# Pre-amp.net
KiCad netlist of a schematic drawn in Altium Designer
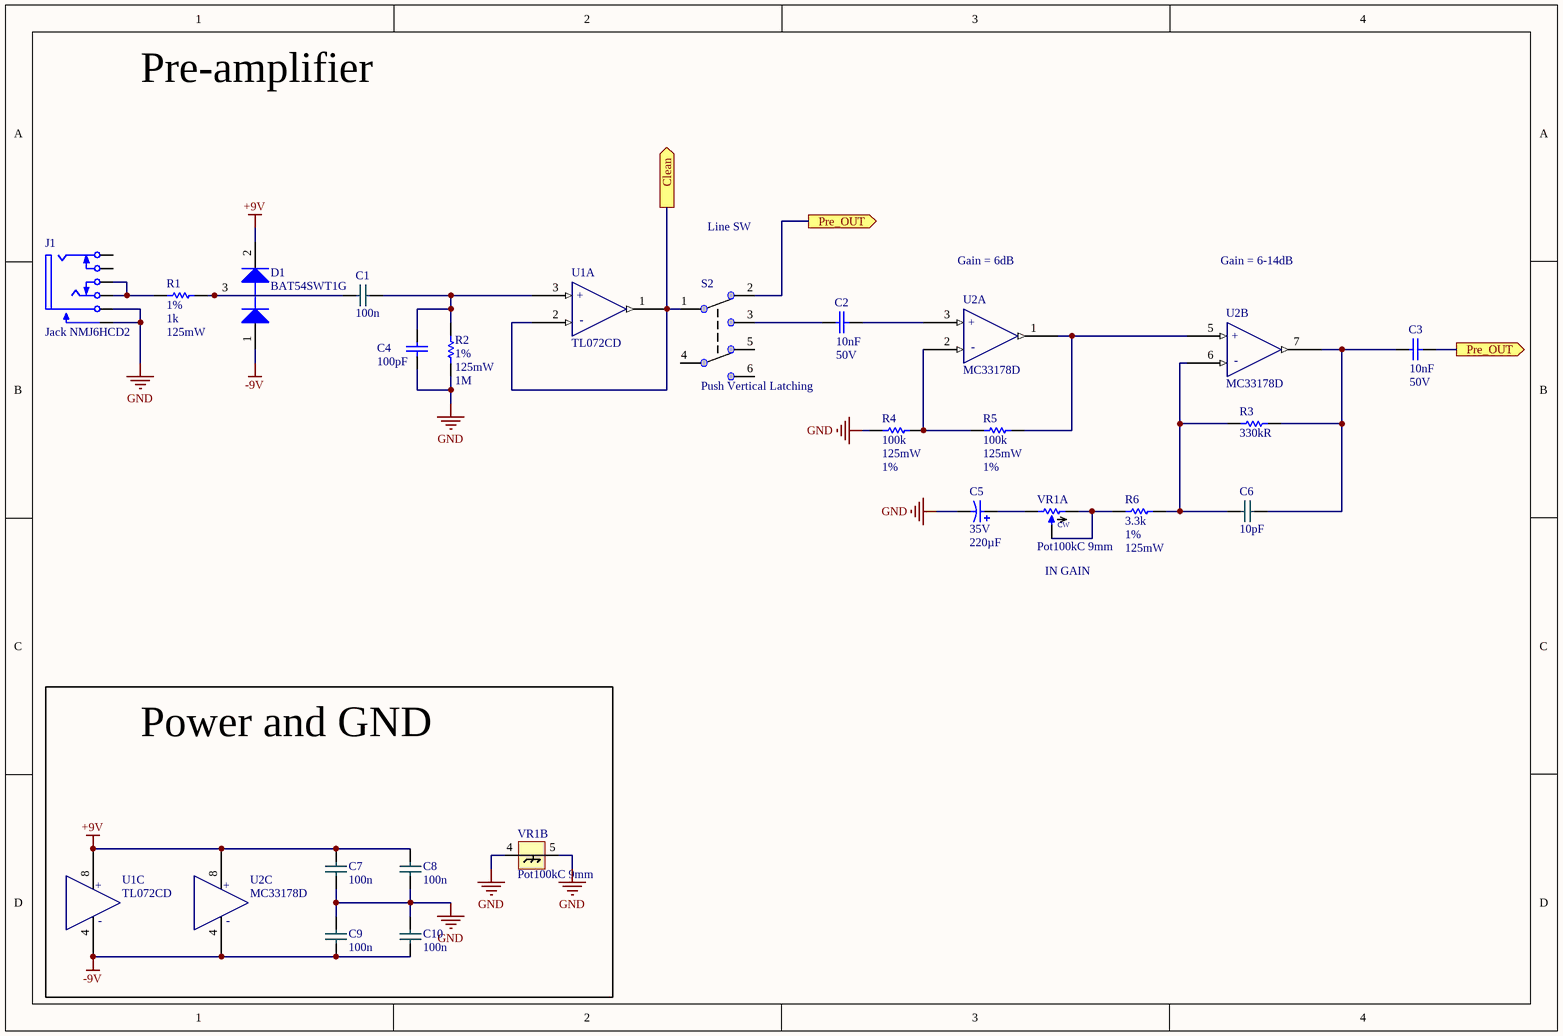
[diagram p0: Pre-amp.SchDoc]

(export (version "E")
  (design (tool "Eeschema 10.0.6"))
  (components
    (comp (ref "C1")
      (value "100n")
      (footprint "0805-CAP")
      (description "0.1uF 25volts C0G 5%")
      (fields
        (field (name "MOUSER PART") "81-GRM31C5C1E104JA01")
        (field (name "Comment") "Cap 0805 100nF 4")
        (field (name "PUBLISHER") "Altium Limited")
      )
      (libsource (lib "Darkglass Electronics") (part "Capacitor NP"))
    )
    (comp (ref "C2")
      (value "Cap 10nF 0805 C0G")
      (footprint "0805-CAP")
      (description "Cap 10nF 0805 C0G 50V +-5%")
      (fields (field (name "CAPACITANCE") "10nF") (field (name "RATED VOLTAGE") "50V"))
      (libsource (lib "Darkglass Electronics") (part "Capacitor Non-polarized"))
    )
    (comp (ref "C3")
      (value "Cap 10nF 0805 C0G")
      (footprint "0805-CAP")
      (description "Cap 10nF 0805 C0G 50V +-5%")
      (fields (field (name "CAPACITANCE") "10nF") (field (name "RATED VOLTAGE") "50V"))
      (libsource (lib "Darkglass Electronics") (part "Capacitor Non-polarized"))
    )
    (comp (ref "C4")
      (value "Cap 100pF 0603 C0G")
      (footprint "0603-CAP")
      (description "Cap 100pF 0603 C0G 50V +-5%")
      (fields (field (name "CAPACITANCE") "100pF"))
      (libsource (lib "Darkglass Electronics") (part "Capacitor Non-polarized"))
    )
    (comp (ref "C5")
      (value "Cap pol 220µF 35V")
      (footprint "E-CAP, SMT, diameter 10mm, height 10.2mm")
      (description "Cap Aluminum 220uF 35V ±20% (10x10.2mm) SMD 2000h 85°C")
      (fields (field (name "RATED VOLTAGE") "35V") (field (name "CAPACITANCE") "220µF"))
      (libsource (lib "Darkglass Electronics") (part "Capacitor Polarized"))
    )
    (comp (ref "C6")
      (value "cap 0805 10pF")
      (footprint "0805-CAP")
      (fields (field (name "CAPACITANCE") "10pF"))
      (libsource (lib "Darkglass Electronics") (part "Capacitor NP"))
    )
    (comp (ref "C7")
      (value "100n")
      (footprint "0805-CAP")
      (description "0.1uF 25volts C0G 5%")
      (fields
        (field (name "MOUSER PART") "81-GRM31C5C1E104JA01")
        (field (name "Comment") "Cap 0805 100nF 4")
        (field (name "PUBLISHER") "Altium Limited")
      )
      (libsource (lib "Darkglass Electronics") (part "Capacitor NP"))
    )
    (comp (ref "C8")
      (value "100n")
      (footprint "0805-CAP")
      (description "0.1uF 25volts C0G 5%")
      (fields
        (field (name "MOUSER PART") "81-GRM31C5C1E104JA01")
        (field (name "Comment") "Cap 0805 100nF 4")
        (field (name "PUBLISHER") "Altium Limited")
      )
      (libsource (lib "Darkglass Electronics") (part "Capacitor NP"))
    )
    (comp (ref "C9")
      (value "100n")
      (footprint "0805-CAP")
      (description "0.1uF 25volts C0G 5%")
      (fields
        (field (name "MOUSER PART") "81-GRM31C5C1E104JA01")
        (field (name "Comment") "Cap 0805 100nF 4")
        (field (name "PUBLISHER") "Altium Limited")
      )
      (libsource (lib "Darkglass Electronics") (part "Capacitor NP"))
    )
    (comp (ref "C10")
      (value "100n")
      (footprint "0805-CAP")
      (description "0.1uF 25volts C0G 5%")
      (fields
        (field (name "MOUSER PART") "81-GRM31C5C1E104JA01")
        (field (name "Comment") "Cap 0805 100nF 4")
        (field (name "PUBLISHER") "Altium Limited")
      )
      (libsource (lib "Darkglass Electronics") (part "Capacitor NP"))
    )
    (comp (ref "D1")
      (value "BAT54SWT1G")
      (footprint "ONSC-SOT-323-3-419-04_V")
      (description "Rectifier Diode, Schottky, 2 Element, 0.2A, 30V V(RRM), Silicon")
      (libsource (lib "Darkglass Electronics") (part "ONSC-D-A1K2C3-3"))
    )
    (comp (ref "J1")
      (value "Jack NMJ6HCD2")
      (footprint "Neutrik Jack metal nut")
      (description "Jack 1/4 stereo switched - PCBH - chrome nut")
      (fields (field (name "MANUFACTURER") "Neutrik") (field (name "DARKGLASS PART") "D00-0011"))
      (libsource (lib "Darkglass Electronics") (part "Symbol"))
    )
    (comp (ref "R1")
      (value "Res 1k 1% 0805")
      (footprint "0805-RES")
      (description "Resistor 1k +-1% 0805 Thin film 0.125W +-50ppm/°C")
      (fields
        (field (name "TOLERANCE (+-)") "1%")
        (field (name "RESISTANCE") "1k")
        (field (name "POWER") "125mW")
      )
      (libsource (lib "Darkglass Electronics") (part "Resistor"))
    )
    (comp (ref "R2")
      (value "Res 1M 1% 0805")
      (footprint "0805-RES")
      (description "Resistor 1M +-1% 0805 Thin film 0.125W +-50ppm/°C")
      (fields
        (field (name "TOLERANCE (+-)") "1%")
        (field (name "POWER") "125mW")
        (field (name "RESISTANCE") "1M")
      )
      (libsource (lib "Darkglass Electronics") (part "Resistor"))
    )
    (comp (ref "R3")
      (value "Res 0805 330k 1%")
      (footprint "0805-RES")
      (description "330kohm, 125mW, 1%, thin film")
      (fields
        (field (name "RESISTANCE") "330kR")
        (field (name "TOLERANCE") "1%")
        (field (name "PUBLISHER") "Altium Limited")
      )
      (libsource (lib "Darkglass Electronics") (part "RES"))
    )
    (comp (ref "R4")
      (value "Res 100k 1% 0805")
      (footprint "0805-RES")
      (description "Resistor 100k +-1% 0805 Thin film 0.125W +-50ppm/°C")
      (fields
        (field (name "RESISTANCE") "100k")
        (field (name "POWER") "125mW")
        (field (name "TOLERANCE (+-)") "1%")
      )
      (libsource (lib "Darkglass Electronics") (part "Resistor"))
    )
    (comp (ref "R5")
      (value "Res 100k 1% 0805")
      (footprint "0805-RES")
      (description "Resistor 100k +-1% 0805 Thin film 0.125W +-50ppm/°C")
      (fields
        (field (name "RESISTANCE") "100k")
        (field (name "POWER") "125mW")
        (field (name "TOLERANCE (+-)") "1%")
      )
      (libsource (lib "Darkglass Electronics") (part "Resistor"))
    )
    (comp (ref "R6")
      (value "Res 3.3k 1% 0805")
      (footprint "0805-RES")
      (description "Resistor 3.3k +-1% 0805 Thin film 0.125W +-50ppm/°C")
      (fields
        (field (name "RESISTANCE") "3.3k")
        (field (name "TOLERANCE (+-)") "1%")
        (field (name "POWER") "125mW")
      )
      (libsource (lib "Darkglass Electronics") (part "Resistor"))
    )
    (comp (ref "S2")
      (value "Push Vertical Latching")
      (footprint "PUSH VERTICAL DPDT")
      (description "DPDT Pushbutton Latching")
      (fields
        (field (name "MANUFACTURER PART NUMBER") "TL2201EEXA")
        (field (name "DARKGLASS PART") "D00-0005")
      )
      (libsource (lib "Darkglass Electronics") (part "Push Vertical"))
    )
    (comp (ref "U1")
      (value "TL072CD")
      (footprint "SOIC8-127P600X175-8N")
      (description "Operational Amplifiers - Op Amps Dual Low Noise JFET SOIC8")
      (libsource (lib "Darkglass Electronics") (part "TL072CD"))
    )
    (comp (ref "U2")
      (value "MC33178D")
      (footprint "SOIC8-127P600X175-8N")
      (description "IC OPAMP GP 5MHZ 8SOIC")
      (fields (field (name "MANUFACTURER") "ON Semiconductor") (field (name "MOUSER PART") "863-MC33178DG"))
      (libsource (lib "") (part "Symbol_1"))
    )
    (comp (ref "VR1")
      (value "Pot100kC 9mm")
      (footprint "LJV 9mm pot")
      (description "LJV 9mm pot")
      (fields (field (name "DARKGLASS PART") "D00-0002"))
      (libsource (lib "") (part "Pot100kC 9mm_1"))
    )
  )
  (nets
    (net (code "1") (name "+9V") (class "Default")
      (node (ref "C7") (pin "2") (pinfunction "2_2") (pintype "passive"))
      (node (ref "C8") (pin "2") (pinfunction "2_2") (pintype "passive"))
      (node (ref "D1") (pin "2") (pinfunction "K_2") (pintype "passive"))
      (node (ref "U1") (pin "8") (pinfunction "V+_8") (pintype "power_in"))
      (node (ref "U2") (pin "8") (pinfunction "8_8") (pintype "power_in"))
    )
    (net (code "2") (name "-9V") (class "Default")
      (node (ref "C10") (pin "1") (pinfunction "1_1") (pintype "passive"))
      (node (ref "C9") (pin "1") (pinfunction "1_1") (pintype "passive"))
      (node (ref "D1") (pin "1") (pinfunction "A_1") (pintype "passive"))
      (node (ref "U1") (pin "4") (pinfunction "V-_4") (pintype "power_in"))
      (node (ref "U2") (pin "4") (pinfunction "4_4") (pintype "power_in"))
    )
    (net (code "3") (name "/Clean") (class "Default")
      (node (ref "S2") (pin "1") (pinfunction "1_1") (pintype "passive"))
      (node (ref "U1") (pin "1") (pinfunction "OUT_1") (pintype "output"))
      (node (ref "U1") (pin "2") (pinfunction "IN-_2") (pintype "input"))
    )
    (net (code "4") (name "/Pre_OUT") (class "Default")
      (node (ref "C3") (pin "2") (pinfunction "2_2") (pintype "passive"))
      (node (ref "S2") (pin "2") (pinfunction "2_2") (pintype "passive"))
    )
    (net (code "5") (name "GND") (class "Default")
      (node (ref "C10") (pin "2") (pinfunction "2_2") (pintype "passive"))
      (node (ref "C4") (pin "2") (pinfunction "2_2") (pintype "passive"))
      (node (ref "C5") (pin "2") (pinfunction "2_2") (pintype "passive"))
      (node (ref "C7") (pin "1") (pinfunction "1_1") (pintype "passive"))
      (node (ref "C8") (pin "1") (pinfunction "1_1") (pintype "passive"))
      (node (ref "C9") (pin "2") (pinfunction "2_2") (pintype "passive"))
      (node (ref "J1") (pin "1") (pinfunction "1_1") (pintype "passive"))
      (node (ref "J1") (pin "6") (pinfunction "6_6") (pintype "passive"))
      (node (ref "R2") (pin "2") (pinfunction "2_2") (pintype "passive"))
      (node (ref "R4") (pin "1") (pinfunction "1_1") (pintype "passive"))
      (node (ref "VR1") (pin "4") (pinfunction "4_4") (pintype "passive"))
      (node (ref "VR1") (pin "5") (pinfunction "5_5") (pintype "passive"))
    )
    (net (code "6") (name "Net-(C2-Pad1)") (class "Default")
      (node (ref "C2") (pin "1") (pinfunction "1_1") (pintype "passive"))
      (node (ref "S2") (pin "3") (pinfunction "3_3") (pintype "passive"))
    )
    (net (code "7") (name "Net-(C2-Pad2)") (class "Default")
      (node (ref "C2") (pin "2") (pinfunction "2_2") (pintype "passive"))
      (node (ref "U2") (pin "3") (pinfunction "3_3") (pintype "input"))
    )
    (net (code "8") (name "Net-(C3-Pad1)") (class "Default")
      (node (ref "C3") (pin "1") (pinfunction "1_1") (pintype "passive"))
      (node (ref "C6") (pin "2") (pinfunction "2_2") (pintype "passive"))
      (node (ref "R3") (pin "2") (pinfunction "2_2") (pintype "passive"))
      (node (ref "U2") (pin "7") (pinfunction "7_7") (pintype "output"))
    )
    (net (code "9") (name "Net-(C6-Pad1)") (class "Default")
      (node (ref "C6") (pin "1") (pinfunction "1_1") (pintype "passive"))
      (node (ref "R3") (pin "1") (pinfunction "1_1") (pintype "passive"))
      (node (ref "R6") (pin "2") (pinfunction "2_2") (pintype "passive"))
      (node (ref "U2") (pin "6") (pinfunction "6_6") (pintype "input"))
    )
    (net (code "10") (name "Net-(D1-K{slash}A)") (class "Default")
      (node (ref "C1") (pin "1") (pinfunction "1_1") (pintype "passive"))
      (node (ref "D1") (pin "3") (pinfunction "K/A_3") (pintype "passive"))
      (node (ref "R1") (pin "2") (pinfunction "2_2") (pintype "passive"))
    )
    (net (code "11") (name "Net-(J1-Pad3)") (class "Default")
      (node (ref "J1") (pin "3") (pinfunction "3_3") (pintype "passive"))
      (node (ref "J1") (pin "4") (pinfunction "4_4") (pintype "passive"))
      (node (ref "R1") (pin "1") (pinfunction "1_1") (pintype "passive"))
    )
    (net (code "12") (name "Net-(R4-Pad2)") (class "Default")
      (node (ref "R4") (pin "2") (pinfunction "2_2") (pintype "passive"))
      (node (ref "R5") (pin "1") (pinfunction "1_1") (pintype "passive"))
      (node (ref "U2") (pin "2") (pinfunction "2_2") (pintype "input"))
    )
    (net (code "13") (name "Net-(R5-Pad2)") (class "Default")
      (node (ref "R5") (pin "2") (pinfunction "2_2") (pintype "passive"))
      (node (ref "U2") (pin "1") (pinfunction "1_1") (pintype "output"))
      (node (ref "U2") (pin "5") (pinfunction "5_5") (pintype "input"))
    )
    (net (code "14") (name "Net-(U1A-IN+)") (class "Default")
      (node (ref "C1") (pin "2") (pinfunction "2_2") (pintype "passive"))
      (node (ref "C4") (pin "1") (pinfunction "1_1") (pintype "passive"))
      (node (ref "R2") (pin "1") (pinfunction "1_1") (pintype "passive"))
      (node (ref "U1") (pin "3") (pinfunction "IN+_3") (pintype "input"))
    )
    (net (code "15") (name "Net-(VR1A-CCWPIN)") (class "Default")
      (node (ref "C5") (pin "1") (pinfunction "1_1") (pintype "passive"))
      (node (ref "VR1") (pin "1") (pinfunction "CCWPIN_1") (pintype "passive"))
    )
    (net (code "16") (name "Net-(VR1A-CWPIN)") (class "Default")
      (node (ref "R6") (pin "1") (pinfunction "1_1") (pintype "passive"))
      (node (ref "VR1") (pin "2") (pinfunction "WIPER_2") (pintype "passive"))
      (node (ref "VR1") (pin "3") (pinfunction "CWPIN_3") (pintype "passive"))
    )
    (net (code "17") (name "unconnected-(J1-Pad2)") (class "Default")
      (node (ref "J1") (pin "2") (pinfunction "2_2") (pintype "passive"))
    )
    (net (code "18") (name "unconnected-(J1-Pad5)") (class "Default")
      (node (ref "J1") (pin "5") (pinfunction "5_5") (pintype "passive"))
    )
    (net (code "19") (name "unconnected-(S2-Pad4)") (class "Default")
      (node (ref "S2") (pin "4") (pinfunction "4_4") (pintype "passive"))
    )
    (net (code "20") (name "unconnected-(S2-Pad5)") (class "Default")
      (node (ref "S2") (pin "5") (pinfunction "5_5") (pintype "passive"))
    )
    (net (code "21") (name "unconnected-(S2-Pad6)") (class "Default")
      (node (ref "S2") (pin "6") (pinfunction "6_6") (pintype "passive"))
    )
  )
)
